# BlinkyTile.net
KiCad netlist of a schematic drawn in EAGLE
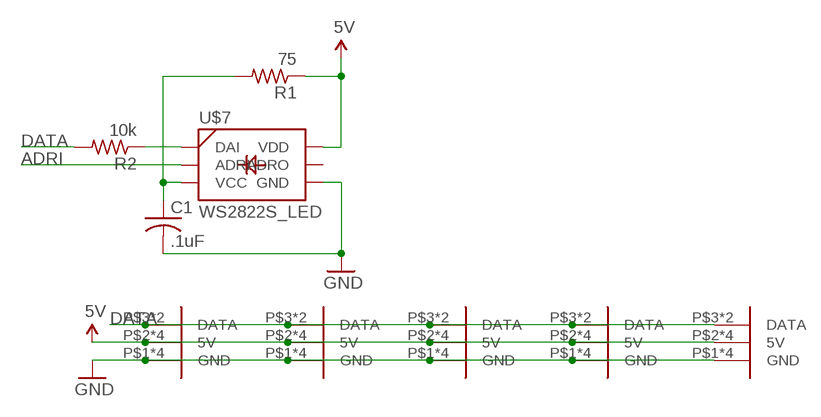
[diagram p0: schematic, sheet 1]

(export (version "E")
  (design (tool "Eeschema 10.0.6"))
  (components
    (comp (ref "C1")
      (value ".1uF")
      (footprint "eagle-import:C0603")
      (libsource (lib "eagle-import") (part "C-USC0603"))
    )
    (comp (ref "R1")
      (value "75")
      (footprint "eagle-import:R0603")
      (libsource (lib "eagle-import") (part "R-US_R0603"))
    )
    (comp (ref "R2")
      (value "10k")
      (footprint "eagle-import:R0603")
      (libsource (lib "eagle-import") (part "R-US_R0603"))
    )
    (comp (ref "U$2")
      (value "D_EDGESLOT")
      (footprint "eagle-import:D_EDGE_SLOT")
      (libsource (lib "eagle-import") (part "D_EDGESLOT"))
    )
    (comp (ref "U$3")
      (value "D_EDGESLOT")
      (footprint "eagle-import:D_EDGE_SLOT")
      (libsource (lib "eagle-import") (part "D_EDGESLOT"))
    )
    (comp (ref "U$4")
      (value "D_EDGESLOT")
      (footprint "eagle-import:D_EDGE_SLOT")
      (libsource (lib "eagle-import") (part "D_EDGESLOT"))
    )
    (comp (ref "U$5")
      (value "D_EDGESLOT")
      (footprint "eagle-import:D_EDGE_SLOT")
      (libsource (lib "eagle-import") (part "D_EDGESLOT"))
    )
    (comp (ref "U$6")
      (value "D_EDGESLOT")
      (footprint "eagle-import:D_EDGE_SLOT")
      (libsource (lib "eagle-import") (part "D_EDGESLOT"))
    )
    (comp (ref "U$7")
      (value "WS2822S_LED")
      (footprint "eagle-import:WS2822S_LED")
      (libsource (lib "eagle-import") (part "WS2822S_LED"))
    )
  )
  (nets
    (net (code "1") (name "/ADRI") (class "Default")
      (node (ref "U$7") (pin "2") (pinfunction "ADRI_2") (pintype "input"))
    )
    (net (code "2") (name "/DATA") (class "Default")
      (node (ref "R2") (pin "2") (pinfunction "2_2") (pintype "passive"))
      (node (ref "U$2") (pin "P$3") (pinfunction "DATA_P$3") (pintype "bidirectional"))
      (node (ref "U$2") (pin "P$8") (pinfunction "DATA_P$8") (pintype "bidirectional"))
      (node (ref "U$3") (pin "P$3") (pinfunction "DATA_P$3") (pintype "bidirectional"))
      (node (ref "U$3") (pin "P$8") (pinfunction "DATA_P$8") (pintype "bidirectional"))
      (node (ref "U$4") (pin "P$3") (pinfunction "DATA_P$3") (pintype "bidirectional"))
      (node (ref "U$4") (pin "P$8") (pinfunction "DATA_P$8") (pintype "bidirectional"))
      (node (ref "U$5") (pin "P$3") (pinfunction "DATA_P$3") (pintype "bidirectional"))
      (node (ref "U$5") (pin "P$8") (pinfunction "DATA_P$8") (pintype "bidirectional"))
      (node (ref "U$6") (pin "P$3") (pinfunction "DATA_P$3") (pintype "bidirectional"))
      (node (ref "U$6") (pin "P$8") (pinfunction "DATA_P$8") (pintype "bidirectional"))
    )
    (net (code "3") (name "5V") (class "Default")
      (node (ref "R1") (pin "1") (pinfunction "1_1") (pintype "passive"))
      (node (ref "U$2") (pin "P$2") (pinfunction "5V_P$2") (pintype "bidirectional"))
      (node (ref "U$2") (pin "P$4") (pinfunction "5V_P$4") (pintype "bidirectional"))
      (node (ref "U$2") (pin "P$7") (pinfunction "5V_P$7") (pintype "bidirectional"))
      (node (ref "U$2") (pin "P$9") (pinfunction "5V_P$9") (pintype "bidirectional"))
      (node (ref "U$3") (pin "P$2") (pinfunction "5V_P$2") (pintype "bidirectional"))
      (node (ref "U$3") (pin "P$4") (pinfunction "5V_P$4") (pintype "bidirectional"))
      (node (ref "U$3") (pin "P$7") (pinfunction "5V_P$7") (pintype "bidirectional"))
      (node (ref "U$3") (pin "P$9") (pinfunction "5V_P$9") (pintype "bidirectional"))
      (node (ref "U$4") (pin "P$2") (pinfunction "5V_P$2") (pintype "bidirectional"))
      (node (ref "U$4") (pin "P$4") (pinfunction "5V_P$4") (pintype "bidirectional"))
      (node (ref "U$4") (pin "P$7") (pinfunction "5V_P$7") (pintype "bidirectional"))
      (node (ref "U$4") (pin "P$9") (pinfunction "5V_P$9") (pintype "bidirectional"))
      (node (ref "U$5") (pin "P$2") (pinfunction "5V_P$2") (pintype "bidirectional"))
      (node (ref "U$5") (pin "P$4") (pinfunction "5V_P$4") (pintype "bidirectional"))
      (node (ref "U$5") (pin "P$7") (pinfunction "5V_P$7") (pintype "bidirectional"))
      (node (ref "U$5") (pin "P$9") (pinfunction "5V_P$9") (pintype "bidirectional"))
      (node (ref "U$6") (pin "P$2") (pinfunction "5V_P$2") (pintype "bidirectional"))
      (node (ref "U$6") (pin "P$4") (pinfunction "5V_P$4") (pintype "bidirectional"))
      (node (ref "U$6") (pin "P$7") (pinfunction "5V_P$7") (pintype "bidirectional"))
      (node (ref "U$6") (pin "P$9") (pinfunction "5V_P$9") (pintype "bidirectional"))
      (node (ref "U$7") (pin "6") (pinfunction "VDD_6") (pintype "power_in"))
    )
    (net (code "4") (name "GND") (class "Default")
      (node (ref "C1") (pin "2") (pinfunction "2_2") (pintype "passive"))
      (node (ref "U$2") (pin "P$1") (pinfunction "GND_P$1") (pintype "bidirectional"))
      (node (ref "U$2") (pin "P$10") (pinfunction "GND_P$10") (pintype "bidirectional"))
      (node (ref "U$2") (pin "P$5") (pinfunction "GND_P$5") (pintype "bidirectional"))
      (node (ref "U$2") (pin "P$6") (pinfunction "GND_P$6") (pintype "bidirectional"))
      (node (ref "U$3") (pin "P$1") (pinfunction "GND_P$1") (pintype "bidirectional"))
      (node (ref "U$3") (pin "P$10") (pinfunction "GND_P$10") (pintype "bidirectional"))
      (node (ref "U$3") (pin "P$5") (pinfunction "GND_P$5") (pintype "bidirectional"))
      (node (ref "U$3") (pin "P$6") (pinfunction "GND_P$6") (pintype "bidirectional"))
      (node (ref "U$4") (pin "P$1") (pinfunction "GND_P$1") (pintype "bidirectional"))
      (node (ref "U$4") (pin "P$10") (pinfunction "GND_P$10") (pintype "bidirectional"))
      (node (ref "U$4") (pin "P$5") (pinfunction "GND_P$5") (pintype "bidirectional"))
      (node (ref "U$4") (pin "P$6") (pinfunction "GND_P$6") (pintype "bidirectional"))
      (node (ref "U$5") (pin "P$1") (pinfunction "GND_P$1") (pintype "bidirectional"))
      (node (ref "U$5") (pin "P$10") (pinfunction "GND_P$10") (pintype "bidirectional"))
      (node (ref "U$5") (pin "P$5") (pinfunction "GND_P$5") (pintype "bidirectional"))
      (node (ref "U$5") (pin "P$6") (pinfunction "GND_P$6") (pintype "bidirectional"))
      (node (ref "U$6") (pin "P$1") (pinfunction "GND_P$1") (pintype "bidirectional"))
      (node (ref "U$6") (pin "P$10") (pinfunction "GND_P$10") (pintype "bidirectional"))
      (node (ref "U$6") (pin "P$5") (pinfunction "GND_P$5") (pintype "bidirectional"))
      (node (ref "U$6") (pin "P$6") (pinfunction "GND_P$6") (pintype "bidirectional"))
      (node (ref "U$7") (pin "4") (pinfunction "GND_4") (pintype "power_in"))
    )
    (net (code "5") (name "Net-(U$7-DAI)") (class "Default")
      (node (ref "R2") (pin "1") (pinfunction "1_1") (pintype "passive"))
      (node (ref "U$7") (pin "1") (pinfunction "DAI_1") (pintype "input"))
    )
    (net (code "6") (name "Net-(U$7-VCC)") (class "Default")
      (node (ref "C1") (pin "1") (pinfunction "1_1") (pintype "passive"))
      (node (ref "R1") (pin "2") (pinfunction "2_2") (pintype "passive"))
      (node (ref "U$7") (pin "3") (pinfunction "VCC_3") (pintype "power_in"))
    )
    (net (code "7") (name "unconnected-(U$7-ADRO-Pad5)") (class "Default")
      (node (ref "U$7") (pin "5") (pinfunction "ADRO_5") (pintype "output"))
    )
  )
)
